# Alimentacao.net
KiCad netlist of a schematic drawn in Altium Designer
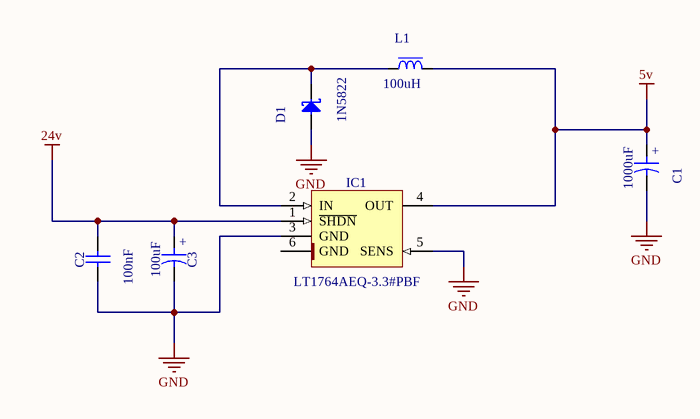
[diagram p0: Alimentacao.SchDoc]

(export (version "E")
  (design (tool "Eeschema 10.0.6"))
  (components
    (comp (ref "C1")
      (value "1000uF")
      (footprint "CAPPR500-1350X2200")
      (description "Polarised capacitor")
      (fields
        (field (name "PART NUMBER") "CAER_1000UF_35V_20%_VISHAY_MAL203850102E3")
        (field (name "VOLTAGE") "35V")
        (field (name "AUTHOR") "CERN DEM JLC")
      )
      (libsource (lib "Capacitors") (part "Capacitor - polarized"))
    )
    (comp (ref "C2")
      (value "100nF")
      (footprint "CAPC2012X135N")
      (description "Non-polarised capacitor")
      (fields
        (field (name "PART NUMBER") "CC0805_100NF_50V_10%_X7R")
        (field (name "VOLTAGE") "50V")
        (field (name "AUTHOR") "CERN DEM JLC")
      )
      (libsource (lib "Capacitors") (part "Capacitor - non polarized"))
    )
    (comp (ref "C3")
      (value "100uF")
      (footprint "CAPPR500-1050X1750")
      (description "Polarised capacitor")
      (fields
        (field (name "PART NUMBER") "CAER_100UF_63V_20%_500-1050X1750_LESR0R190")
        (field (name "VOLTAGE") "63V")
        (field (name "AUTHOR") "CERN DEM JLC")
      )
      (libsource (lib "Capacitors") (part "Capacitor - polarized"))
    )
    (comp (ref "D1")
      (value "1N5822")
      (footprint "DO-201AD")
      (description "Schottky Diode")
      (fields
        (field (name "VOLTAGE") "40V")
        (field (name "POWER") "3A")
        (field (name "AUTHOR") "CERN DEM JLC")
      )
      (libsource (lib "ICs And Semiconductors") (part "Diode Schottky"))
    )
    (comp (ref "IC1")
      (value "LT1764AEQ-3.3#PBF")
      (footprint "TO170P1394X457-6N-R900X1060")
      (description "3A, Fast Transient Response, Low Noise, LDO Regulators")
      (fields (field (name "MANUFACTURER") "LINEAR TECHNOLOGY") (field (name "AUTHOR") "CERN DEM JLC"))
      (libsource (lib "ICs And Semiconductors") (part "LT1764AEQ-X.X"))
    )
    (comp (ref "L1")
      (value "100uH")
      (footprint "IND_WURTH_WE-PD4_L")
      (description "Inductor With Magnetic core")
      (fields
        (field (name "PART NUMBER") "IND_3.3UH_20%_WURTH_WE-PD4_74456033")
        (field (name "POWER") "5.3A")
        (field (name "AUTHOR") "CERN DEM JLC")
      )
      (libsource (lib "Inductors & Transformers") (part "Inductor With Magnetic core"))
    )
  )
  (nets
    (net (code "1") (name "5v") (class "Default")
      (node (ref "C1") (pin "1") (pinfunction "1_1") (pintype "passive"))
      (node (ref "IC1") (pin "4") (pinfunction "OUT_4") (pintype "power_in"))
      (node (ref "L1") (pin "2") (pinfunction "2_2") (pintype "passive"))
    )
    (net (code "2") (name "24v") (class "Default")
      (node (ref "C2") (pin "2") (pinfunction "2_2") (pintype "passive"))
      (node (ref "C3") (pin "1") (pinfunction "1_1") (pintype "passive"))
      (node (ref "IC1") (pin "1") (pinfunction "~{SHDN}_1") (pintype "input"))
    )
    (net (code "3") (name "GND") (class "Default")
      (node (ref "C1") (pin "2") (pinfunction "2_2") (pintype "passive"))
      (node (ref "C2") (pin "1") (pinfunction "1_1") (pintype "passive"))
      (node (ref "C3") (pin "2") (pinfunction "2_2") (pintype "passive"))
      (node (ref "D1") (pin "2") (pinfunction "A_2") (pintype "passive"))
      (node (ref "IC1") (pin "3") (pinfunction "GND_3") (pintype "power_in"))
      (node (ref "IC1") (pin "5") (pinfunction "SENS_5") (pintype "input"))
    )
    (net (code "4") (name "Net-(D1-C)") (class "Default")
      (node (ref "D1") (pin "1") (pinfunction "C_1") (pintype "passive"))
      (node (ref "IC1") (pin "2") (pinfunction "IN_2") (pintype "input"))
      (node (ref "L1") (pin "1") (pinfunction "1_1") (pintype "passive"))
    )
    (net (code "5") (name "unconnected-(IC1-GND-Pad6)") (class "Default")
      (node (ref "IC1") (pin "6") (pinfunction "GND_6") (pintype "power_in"))
    )
  )
)
